# Wheel_Encoder_Adapter_Schmitt.net
KiCad netlist of a schematic drawn in EAGLE
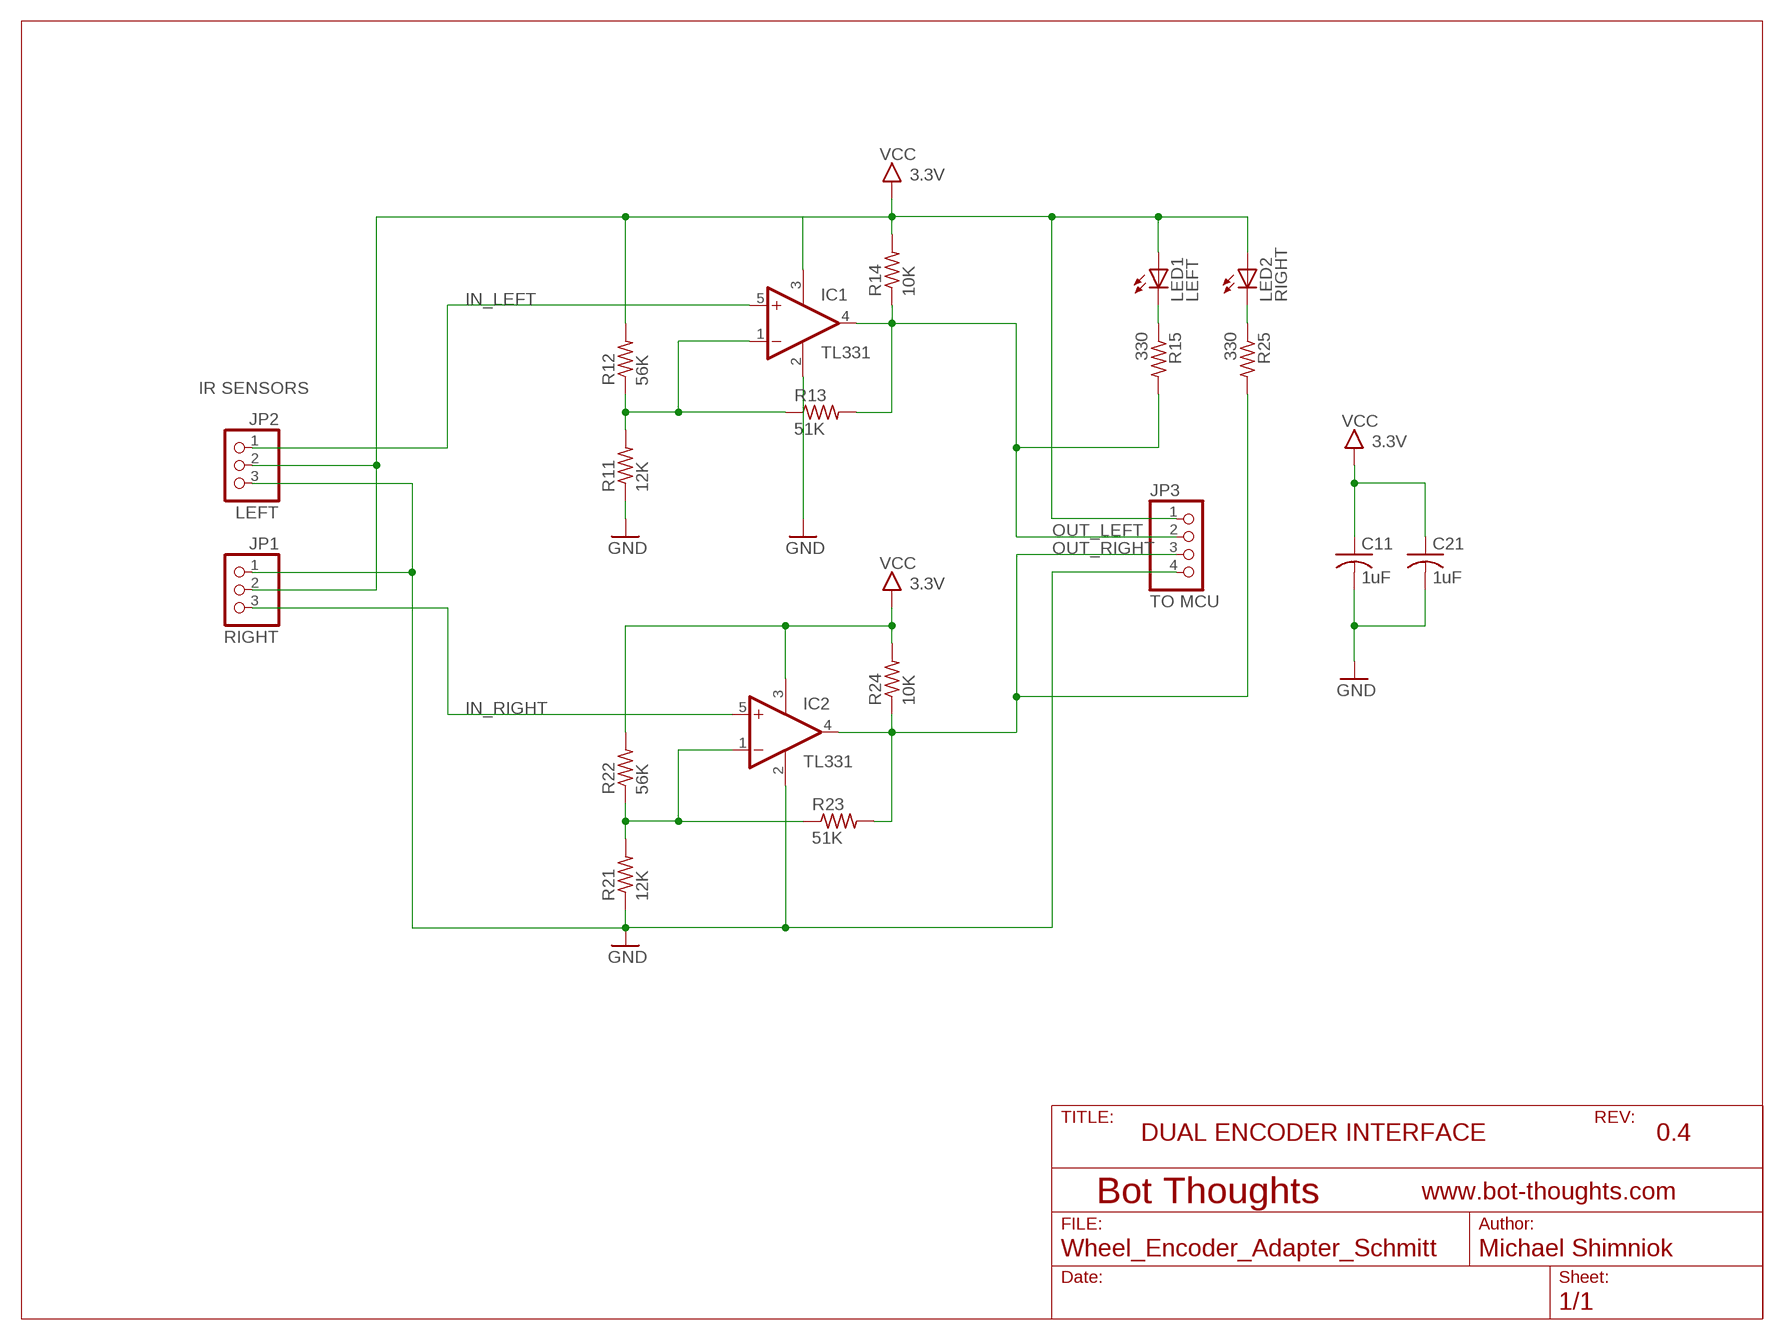
[diagram p0: schematic, sheet 1]

(export (version "E")
  (design (tool "Eeschema 10.0.6"))
  (components
    (comp (ref "C11")
      (value "1uF")
      (footprint "eagle-import:C0603")
      (fields (field (name "PARTNO") "C1608X7R1A105M"))
      (libsource (lib "eagle-import") (part "C-USC0603"))
    )
    (comp (ref "C21")
      (value "1uF")
      (footprint "eagle-import:C0603")
      (fields (field (name "PARTNO") "C1608X7R1A105M"))
      (libsource (lib "eagle-import") (part "C-USC0603"))
    )
    (comp (ref "IC1")
      (value "TL331")
      (footprint "eagle-import:DBV-R-PDSO-G5")
      (fields (field (name "PARTNO") "TL331IDBVR"))
      (libsource (lib "eagle-import") (part "TL331"))
    )
    (comp (ref "IC2")
      (value "TL331")
      (footprint "eagle-import:DBV-R-PDSO-G5")
      (fields (field (name "PARTNO") "TL331IDBVR"))
      (libsource (lib "eagle-import") (part "TL331"))
    )
    (comp (ref "JP1")
      (value "RIGHT")
      (footprint "eagle-import:1X03-S")
      (libsource (lib "eagle-import") (part "PINHD-1X03_2.54-S"))
    )
    (comp (ref "JP2")
      (value "LEFT")
      (footprint "eagle-import:1X03-S")
      (libsource (lib "eagle-import") (part "PINHD-1X03_2.54-S"))
    )
    (comp (ref "JP3")
      (value "TO MCU")
      (footprint "eagle-import:1X04-S")
      (libsource (lib "eagle-import") (part "PINHD-1X04_2.54-S"))
    )
    (comp (ref "LED1")
      (value "LEFT")
      (footprint "eagle-import:CHIPLED_1206")
      (fields (field (name "PARTNO") "LG N971-KN-1"))
      (libsource (lib "eagle-import") (part "LEDCHIPLED_1206"))
    )
    (comp (ref "LED2")
      (value "RIGHT")
      (footprint "eagle-import:CHIPLED_1206")
      (fields (field (name "PARTNO") "LG N971-KN-1"))
      (libsource (lib "eagle-import") (part "LEDCHIPLED_1206"))
    )
    (comp (ref "R11")
      (value "12K")
      (footprint "eagle-import:R0603")
      (fields (field (name "PARTNO") "ERJ-3EKF1202V"))
      (libsource (lib "eagle-import") (part "R-US_R0603"))
    )
    (comp (ref "R12")
      (value "56K")
      (footprint "eagle-import:R0603")
      (fields (field (name "PARTNO") "ERJ-3EKF5602V"))
      (libsource (lib "eagle-import") (part "R-US_R0603"))
    )
    (comp (ref "R13")
      (value "51K")
      (footprint "eagle-import:R0603")
      (fields (field (name "PARTNO") "ERJ-3EKF5102V"))
      (libsource (lib "eagle-import") (part "R-US_R0603"))
    )
    (comp (ref "R14")
      (value "10K")
      (footprint "eagle-import:R0603")
      (fields (field (name "PARTNO") "ERJ-3GEYJ103V"))
      (libsource (lib "eagle-import") (part "R-US_R0603"))
    )
    (comp (ref "R15")
      (value "330")
      (footprint "eagle-import:R0603")
      (fields (field (name "PARTNO") "ERJ-3GEYJ331V"))
      (libsource (lib "eagle-import") (part "R-US_R0603"))
    )
    (comp (ref "R21")
      (value "12K")
      (footprint "eagle-import:R0603")
      (fields (field (name "PARTNO") "ERJ-3EKF1202V"))
      (libsource (lib "eagle-import") (part "R-US_R0603"))
    )
    (comp (ref "R22")
      (value "56K")
      (footprint "eagle-import:R0603")
      (fields (field (name "PARTNO") "ERJ-3EKF5602V"))
      (libsource (lib "eagle-import") (part "R-US_R0603"))
    )
    (comp (ref "R23")
      (value "51K")
      (footprint "eagle-import:R0603")
      (fields (field (name "PARTNO") "ERJ-3EKF5102V"))
      (libsource (lib "eagle-import") (part "R-US_R0603"))
    )
    (comp (ref "R24")
      (value "10K")
      (footprint "eagle-import:R0603")
      (fields (field (name "PARTNO") "ERJ-3GEYJ103V"))
      (libsource (lib "eagle-import") (part "R-US_R0603"))
    )
    (comp (ref "R25")
      (value "330")
      (footprint "eagle-import:R0603")
      (fields (field (name "PARTNO") "ERJ-3GEYJ331V"))
      (libsource (lib "eagle-import") (part "R-US_R0603"))
    )
  )
  (nets
    (net (code "1") (name "/IN_LEFT") (class "Default")
      (node (ref "IC1") (pin "5") (pinfunction "+IN_5") (pintype "input"))
      (node (ref "JP2") (pin "1") (pinfunction "1_1") (pintype "passive"))
    )
    (net (code "2") (name "/IN_RIGHT") (class "Default")
      (node (ref "IC2") (pin "5") (pinfunction "+IN_5") (pintype "input"))
      (node (ref "JP1") (pin "3") (pinfunction "3_3") (pintype "passive"))
    )
    (net (code "3") (name "/OUT_LEFT") (class "Default")
      (node (ref "IC1") (pin "4") (pinfunction "OUT_4") (pintype "output"))
      (node (ref "JP3") (pin "2") (pinfunction "2_2") (pintype "passive"))
      (node (ref "R13") (pin "2") (pinfunction "2_2") (pintype "passive"))
      (node (ref "R14") (pin "1") (pinfunction "1_1") (pintype "passive"))
      (node (ref "R15") (pin "2") (pinfunction "2_2") (pintype "passive"))
    )
    (net (code "4") (name "/OUT_RIGHT") (class "Default")
      (node (ref "IC2") (pin "4") (pinfunction "OUT_4") (pintype "output"))
      (node (ref "JP3") (pin "3") (pinfunction "3_3") (pintype "passive"))
      (node (ref "R23") (pin "2") (pinfunction "2_2") (pintype "passive"))
      (node (ref "R24") (pin "1") (pinfunction "1_1") (pintype "passive"))
      (node (ref "R25") (pin "2") (pinfunction "2_2") (pintype "passive"))
    )
    (net (code "5") (name "3.3V") (class "Default")
      (node (ref "C11") (pin "1") (pinfunction "1_1") (pintype "passive"))
      (node (ref "C21") (pin "1") (pinfunction "1_1") (pintype "passive"))
      (node (ref "IC1") (pin "3") (pinfunction "V+_3") (pintype "power_in"))
      (node (ref "IC2") (pin "3") (pinfunction "V+_3") (pintype "power_in"))
      (node (ref "JP1") (pin "2") (pinfunction "2_2") (pintype "passive"))
      (node (ref "JP2") (pin "2") (pinfunction "2_2") (pintype "passive"))
      (node (ref "JP3") (pin "1") (pinfunction "1_1") (pintype "passive"))
      (node (ref "LED1") (pin "A") (pinfunction "A_A") (pintype "passive"))
      (node (ref "LED2") (pin "A") (pinfunction "A_A") (pintype "passive"))
      (node (ref "R12") (pin "2") (pinfunction "2_2") (pintype "passive"))
      (node (ref "R14") (pin "2") (pinfunction "2_2") (pintype "passive"))
      (node (ref "R22") (pin "2") (pinfunction "2_2") (pintype "passive"))
      (node (ref "R24") (pin "2") (pinfunction "2_2") (pintype "passive"))
    )
    (net (code "6") (name "GND") (class "Default")
      (node (ref "C11") (pin "2") (pinfunction "2_2") (pintype "passive"))
      (node (ref "C21") (pin "2") (pinfunction "2_2") (pintype "passive"))
      (node (ref "IC1") (pin "2") (pinfunction "GND_2") (pintype "power_in"))
      (node (ref "IC2") (pin "2") (pinfunction "GND_2") (pintype "power_in"))
      (node (ref "JP1") (pin "1") (pinfunction "1_1") (pintype "passive"))
      (node (ref "JP2") (pin "3") (pinfunction "3_3") (pintype "passive"))
      (node (ref "JP3") (pin "4") (pinfunction "4_4") (pintype "passive"))
      (node (ref "R11") (pin "1") (pinfunction "1_1") (pintype "passive"))
      (node (ref "R21") (pin "1") (pinfunction "1_1") (pintype "passive"))
    )
    (net (code "7") (name "Net-(IC1--IN)") (class "Default")
      (node (ref "IC1") (pin "1") (pinfunction "-IN_1") (pintype "input"))
      (node (ref "R11") (pin "2") (pinfunction "2_2") (pintype "passive"))
      (node (ref "R12") (pin "1") (pinfunction "1_1") (pintype "passive"))
      (node (ref "R13") (pin "1") (pinfunction "1_1") (pintype "passive"))
    )
    (net (code "8") (name "Net-(IC2--IN)") (class "Default")
      (node (ref "IC2") (pin "1") (pinfunction "-IN_1") (pintype "input"))
      (node (ref "R21") (pin "2") (pinfunction "2_2") (pintype "passive"))
      (node (ref "R22") (pin "1") (pinfunction "1_1") (pintype "passive"))
      (node (ref "R23") (pin "1") (pinfunction "1_1") (pintype "passive"))
    )
    (net (code "9") (name "Net-(LED1-PadC)") (class "Default")
      (node (ref "LED1") (pin "C") (pinfunction "C_C") (pintype "passive"))
      (node (ref "R15") (pin "1") (pinfunction "1_1") (pintype "passive"))
    )
    (net (code "10") (name "Net-(LED2-PadC)") (class "Default")
      (node (ref "LED2") (pin "C") (pinfunction "C_C") (pintype "passive"))
      (node (ref "R25") (pin "1") (pinfunction "1_1") (pintype "passive"))
    )
  )
)
